# LCD_Keypad.net
KiCad netlist of a schematic drawn in Altium Designer
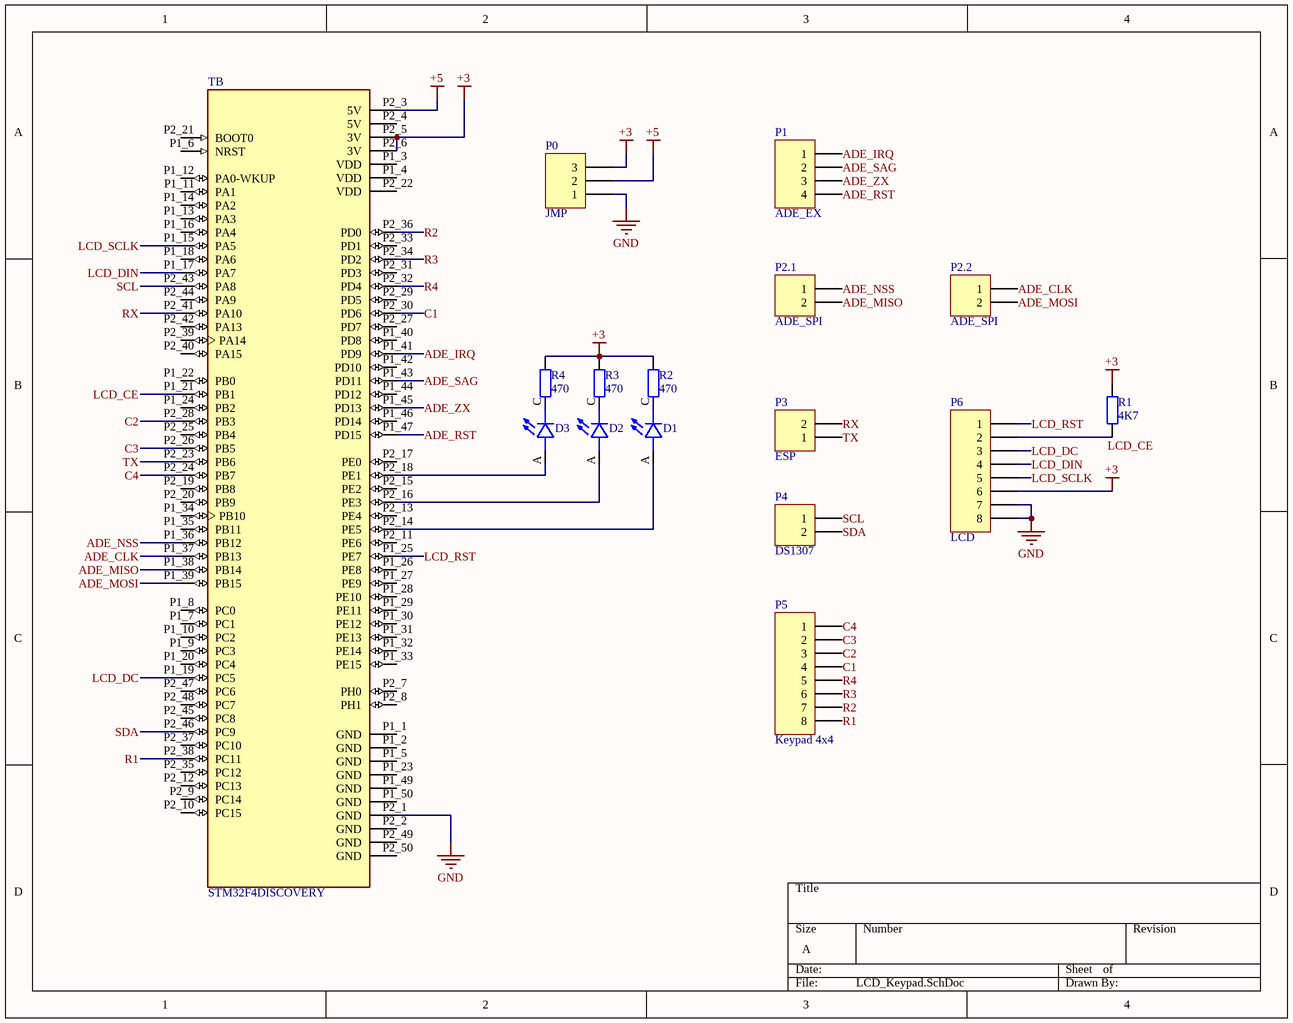
[diagram p0: LCD_Keypad.SchDoc]

(export (version "E")
  (design (tool "Eeschema 10.0.6"))
  (components
    (comp (ref "D1")
      (value "L08R5000Q1")
      (footprint "LEDRD254W57D500H1070")
      (description "LED, Orange, Through Hole, T-1 3/4 (5mm), 30 mA, 2.1 V, 635 nm")
      (fields (field (name "MF") "{'manufacturer': u'LED Technology'}"))
      (libsource (lib "LED_L08R5000Q1") (part "L08R5000Q1"))
    )
    (comp (ref "D2")
      (value "L08R5000Q1")
      (footprint "LEDRD254W57D500H1070")
      (description "LED, Orange, Through Hole, T-1 3/4 (5mm), 30 mA, 2.1 V, 635 nm")
      (fields (field (name "MF") "{'manufacturer': u'LED Technology'}"))
      (libsource (lib "LED_L08R5000Q1") (part "L08R5000Q1"))
    )
    (comp (ref "D3")
      (value "L08R5000Q1")
      (footprint "LEDRD254W57D500H1070")
      (description "LED, Orange, Through Hole, T-1 3/4 (5mm), 30 mA, 2.1 V, 635 nm")
      (fields (field (name "MF") "{'manufacturer': u'LED Technology'}"))
      (libsource (lib "LED_L08R5000Q1") (part "L08R5000Q1"))
    )
    (comp (ref "P0")
      (value "JMP")
      (footprint "HDR1X3")
      (description "Header, 3-Pin")
      (fields (field (name "PUBLISHER") "Altium Limited"))
      (libsource (lib "Miscellaneous Connectors") (part "Header 3"))
    )
    (comp (ref "P1")
      (value "ADE_EX")
      (footprint "HDR1X4")
      (description "Header, 4-Pin")
      (fields (field (name "PUBLISHER") "Altium Limited"))
      (libsource (lib "Miscellaneous Connectors") (part "Header 4"))
    )
    (comp (ref "P2.1")
      (value "ADE_SPI")
      (footprint "HDR1X2")
      (description "Header, 2-Pin")
      (fields (field (name "PUBLISHER") "Altium Limited"))
      (libsource (lib "Miscellaneous Connectors") (part "Header 2"))
    )
    (comp (ref "P2.2")
      (value "ADE_SPI")
      (footprint "HDR1X2")
      (description "Header, 2-Pin")
      (fields (field (name "PUBLISHER") "Altium Limited"))
      (libsource (lib "Miscellaneous Connectors") (part "Header 2"))
    )
    (comp (ref "P3")
      (value "ESP")
      (footprint "HDR1X2")
      (description "Header, 2-Pin")
      (fields (field (name "PUBLISHER") "Altium Limited"))
      (libsource (lib "") (part "Header 2_1"))
    )
    (comp (ref "P4")
      (value "DS1307")
      (footprint "HDR1X2")
      (description "Header, 2-Pin")
      (fields (field (name "PUBLISHER") "Altium Limited"))
      (libsource (lib "Miscellaneous Connectors") (part "Header 2"))
    )
    (comp (ref "P5")
      (value "Keypad 4x4")
      (footprint "HDR1X8")
      (description "Header, 8-Pin")
      (fields (field (name "PUBLISHER") "Altium Limited"))
      (libsource (lib "Miscellaneous Connectors") (part "Header 8"))
    )
    (comp (ref "P6")
      (value "LCD")
      (footprint "HDR1X8")
      (description "Header, 8-Pin")
      (fields (field (name "PUBLISHER") "Altium Limited"))
      (libsource (lib "Miscellaneous Connectors") (part "Header 8"))
    )
    (comp (ref "R1")
      (value "4K7")
      (footprint "AXIAL-0.4")
      (description "Resistor")
      (fields (field (name "Comment") "Res2") (field (name "PUBLISHER") "Altium Limited"))
      (libsource (lib "") (part "Res2_1"))
    )
    (comp (ref "R2")
      (value "470")
      (footprint "AXIAL-0.4")
      (description "Resistor")
      (fields (field (name "Comment") "Res2") (field (name "PUBLISHER") "Altium Limited"))
      (libsource (lib "Miscellaneous Devices") (part "Res2"))
    )
    (comp (ref "R3")
      (value "470")
      (footprint "AXIAL-0.4")
      (description "Resistor")
      (fields (field (name "Comment") "Res2") (field (name "PUBLISHER") "Altium Limited"))
      (libsource (lib "Miscellaneous Devices") (part "Res2"))
    )
    (comp (ref "R4")
      (value "470")
      (footprint "AXIAL-0.4")
      (description "Resistor")
      (fields (field (name "Comment") "Res2") (field (name "PUBLISHER") "Altium Limited"))
      (libsource (lib "Miscellaneous Devices") (part "Res2"))
    )
    (comp (ref "TB")
      (value "STM32F4DISCOVERY")
      (footprint "MODULE_STM32F4DISCOVERY")
      (description "STM32F407VGT6 Discovery STM32F4 ARMÂ® CortexÂ®-M4 MCU 32-Bit Embedded Evaluation Board")
      (fields (field (name "MF") "STMicroelectronics"))
      (libsource (lib "STM32F4DISCOVERY") (part "STM32F4DISCOVERY"))
    )
  )
  (nets
    (net (code "1") (name "+3") (class "Default")
      (node (ref "P0") (pin "3") (pinfunction "3_3") (pintype "passive"))
      (node (ref "P6") (pin "6") (pinfunction "6_6") (pintype "passive"))
      (node (ref "R1") (pin "2") (pinfunction "2_2") (pintype "passive"))
      (node (ref "R2") (pin "1") (pinfunction "1_1") (pintype "passive"))
      (node (ref "R3") (pin "1") (pinfunction "1_1") (pintype "passive"))
      (node (ref "R4") (pin "1") (pinfunction "1_1") (pintype "passive"))
      (node (ref "TB") (pin "P2_5") (pinfunction "3V_P2_5") (pintype "power_in"))
      (node (ref "TB") (pin "P2_6") (pinfunction "3V_P2_6") (pintype "power_in"))
    )
    (net (code "2") (name "+5") (class "Default")
      (node (ref "P0") (pin "2") (pinfunction "2_2") (pintype "passive"))
      (node (ref "TB") (pin "P2_3") (pinfunction "5V_P2_3") (pintype "power_in"))
    )
    (net (code "3") (name "/ADE_CLK") (class "Default")
      (node (ref "P2.2") (pin "1") (pinfunction "1_1") (pintype "passive"))
      (node (ref "TB") (pin "P1_37") (pinfunction "PB13_P1_37") (pintype "bidirectional"))
    )
    (net (code "4") (name "/ADE_IRQ") (class "Default")
      (node (ref "P1") (pin "1") (pinfunction "1_1") (pintype "passive"))
      (node (ref "TB") (pin "P1_41") (pinfunction "PD9_P1_41") (pintype "bidirectional"))
    )
    (net (code "5") (name "/ADE_MISO") (class "Default")
      (node (ref "P2.1") (pin "2") (pinfunction "2_2") (pintype "passive"))
      (node (ref "TB") (pin "P1_38") (pinfunction "PB14_P1_38") (pintype "bidirectional"))
    )
    (net (code "6") (name "/ADE_MOSI") (class "Default")
      (node (ref "P2.2") (pin "2") (pinfunction "2_2") (pintype "passive"))
      (node (ref "TB") (pin "P1_39") (pinfunction "PB15_P1_39") (pintype "bidirectional"))
    )
    (net (code "7") (name "/ADE_NSS") (class "Default")
      (node (ref "P2.1") (pin "1") (pinfunction "1_1") (pintype "passive"))
      (node (ref "TB") (pin "P1_36") (pinfunction "PB12_P1_36") (pintype "bidirectional"))
    )
    (net (code "8") (name "/ADE_RST") (class "Default")
      (node (ref "P1") (pin "4") (pinfunction "4_4") (pintype "passive"))
      (node (ref "TB") (pin "P1_47") (pinfunction "PD15_P1_47") (pintype "bidirectional"))
    )
    (net (code "9") (name "/ADE_SAG") (class "Default")
      (node (ref "P1") (pin "2") (pinfunction "2_2") (pintype "passive"))
      (node (ref "TB") (pin "P1_43") (pinfunction "PD11_P1_43") (pintype "bidirectional"))
    )
    (net (code "10") (name "/ADE_ZX") (class "Default")
      (node (ref "P1") (pin "3") (pinfunction "3_3") (pintype "passive"))
      (node (ref "TB") (pin "P1_45") (pinfunction "PD13_P1_45") (pintype "bidirectional"))
    )
    (net (code "11") (name "/C1") (class "Default")
      (node (ref "P5") (pin "4") (pinfunction "4_4") (pintype "passive"))
      (node (ref "TB") (pin "P2_30") (pinfunction "PD6_P2_30") (pintype "bidirectional"))
    )
    (net (code "12") (name "/C2") (class "Default")
      (node (ref "P5") (pin "3") (pinfunction "3_3") (pintype "passive"))
      (node (ref "TB") (pin "P2_28") (pinfunction "PB3_P2_28") (pintype "bidirectional"))
    )
    (net (code "13") (name "/C3") (class "Default")
      (node (ref "P5") (pin "2") (pinfunction "2_2") (pintype "passive"))
      (node (ref "TB") (pin "P2_26") (pinfunction "PB5_P2_26") (pintype "bidirectional"))
    )
    (net (code "14") (name "/C4") (class "Default")
      (node (ref "P5") (pin "1") (pinfunction "1_1") (pintype "passive"))
      (node (ref "TB") (pin "P2_24") (pinfunction "PB7_P2_24") (pintype "bidirectional"))
    )
    (net (code "15") (name "/LCD_CE") (class "Default")
      (node (ref "P6") (pin "2") (pinfunction "2_2") (pintype "passive"))
      (node (ref "R1") (pin "1") (pinfunction "1_1") (pintype "passive"))
      (node (ref "TB") (pin "P1_21") (pinfunction "PB1_P1_21") (pintype "bidirectional"))
    )
    (net (code "16") (name "/LCD_DC") (class "Default")
      (node (ref "P6") (pin "3") (pinfunction "3_3") (pintype "passive"))
      (node (ref "TB") (pin "P1_19") (pinfunction "PC5_P1_19") (pintype "bidirectional"))
    )
    (net (code "17") (name "/LCD_DIN") (class "Default")
      (node (ref "P6") (pin "4") (pinfunction "4_4") (pintype "passive"))
      (node (ref "TB") (pin "P1_17") (pinfunction "PA7_P1_17") (pintype "bidirectional"))
    )
    (net (code "18") (name "/LCD_RST") (class "Default")
      (node (ref "P6") (pin "1") (pinfunction "1_1") (pintype "passive"))
      (node (ref "TB") (pin "P1_25") (pinfunction "PE7_P1_25") (pintype "bidirectional"))
    )
    (net (code "19") (name "/LCD_SCLK") (class "Default")
      (node (ref "P6") (pin "5") (pinfunction "5_5") (pintype "passive"))
      (node (ref "TB") (pin "P1_15") (pinfunction "PA5_P1_15") (pintype "bidirectional"))
    )
    (net (code "20") (name "/R1") (class "Default")
      (node (ref "P5") (pin "8") (pinfunction "8_8") (pintype "passive"))
      (node (ref "TB") (pin "P2_38") (pinfunction "PC11_P2_38") (pintype "bidirectional"))
    )
    (net (code "21") (name "/R2") (class "Default")
      (node (ref "P5") (pin "7") (pinfunction "7_7") (pintype "passive"))
      (node (ref "TB") (pin "P2_36") (pinfunction "PD0_P2_36") (pintype "bidirectional"))
    )
    (net (code "22") (name "/R3") (class "Default")
      (node (ref "P5") (pin "6") (pinfunction "6_6") (pintype "passive"))
      (node (ref "TB") (pin "P2_34") (pinfunction "PD2_P2_34") (pintype "bidirectional"))
    )
    (net (code "23") (name "/R4") (class "Default")
      (node (ref "P5") (pin "5") (pinfunction "5_5") (pintype "passive"))
      (node (ref "TB") (pin "P2_32") (pinfunction "PD4_P2_32") (pintype "bidirectional"))
    )
    (net (code "24") (name "/RX") (class "Default")
      (node (ref "P3") (pin "2") (pinfunction "2_2") (pintype "passive"))
      (node (ref "TB") (pin "P2_41") (pinfunction "PA10_P2_41") (pintype "bidirectional"))
    )
    (net (code "25") (name "/SCL") (class "Default")
      (node (ref "P4") (pin "1") (pinfunction "1_1") (pintype "passive"))
      (node (ref "TB") (pin "P2_43") (pinfunction "PA8_P2_43") (pintype "bidirectional"))
    )
    (net (code "26") (name "/SDA") (class "Default")
      (node (ref "P4") (pin "2") (pinfunction "2_2") (pintype "passive"))
      (node (ref "TB") (pin "P2_46") (pinfunction "PC9_P2_46") (pintype "bidirectional"))
    )
    (net (code "27") (name "/TX") (class "Default")
      (node (ref "P3") (pin "1") (pinfunction "1_1") (pintype "passive"))
      (node (ref "TB") (pin "P2_23") (pinfunction "PB6_P2_23") (pintype "bidirectional"))
    )
    (net (code "28") (name "GND") (class "Default")
      (node (ref "P0") (pin "1") (pinfunction "1_1") (pintype "passive"))
      (node (ref "P6") (pin "7") (pinfunction "7_7") (pintype "passive"))
      (node (ref "P6") (pin "8") (pinfunction "8_8") (pintype "passive"))
      (node (ref "TB") (pin "P2_1") (pinfunction "GND_P2_1") (pintype "power_in"))
    )
    (net (code "29") (name "Net-(D1-PadC)") (class "Default")
      (node (ref "D1") (pin "C") (pinfunction "C_C") (pintype "passive"))
      (node (ref "R2") (pin "2") (pinfunction "2_2") (pintype "passive"))
    )
    (net (code "30") (name "Net-(D2-PadC)") (class "Default")
      (node (ref "D2") (pin "C") (pinfunction "C_C") (pintype "passive"))
      (node (ref "R3") (pin "2") (pinfunction "2_2") (pintype "passive"))
    )
    (net (code "31") (name "Net-(D3-PadC)") (class "Default")
      (node (ref "D3") (pin "C") (pinfunction "C_C") (pintype "passive"))
      (node (ref "R4") (pin "2") (pinfunction "2_2") (pintype "passive"))
    )
    (net (code "32") (name "Net-(TB-PE1)") (class "Default")
      (node (ref "D3") (pin "A") (pinfunction "A_A") (pintype "passive"))
      (node (ref "TB") (pin "P2_18") (pinfunction "PE1_P2_18") (pintype "bidirectional"))
    )
    (net (code "33") (name "Net-(TB-PE3)") (class "Default")
      (node (ref "D2") (pin "A") (pinfunction "A_A") (pintype "passive"))
      (node (ref "TB") (pin "P2_16") (pinfunction "PE3_P2_16") (pintype "bidirectional"))
    )
    (net (code "34") (name "Net-(TB-PE5)") (class "Default")
      (node (ref "D1") (pin "A") (pinfunction "A_A") (pintype "passive"))
      (node (ref "TB") (pin "P2_14") (pinfunction "PE5_P2_14") (pintype "bidirectional"))
    )
    (net (code "35") (name "unconnected-(TB-5V-PadP2_4)") (class "Default")
      (node (ref "TB") (pin "P2_4") (pinfunction "5V_P2_4") (pintype "power_in"))
    )
    (net (code "36") (name "unconnected-(TB-BOOT0-PadP2_21)") (class "Default")
      (node (ref "TB") (pin "P2_21") (pinfunction "BOOT0_P2_21") (pintype "input"))
    )
    (net (code "37") (name "unconnected-(TB-GND-PadP1_1)") (class "Default")
      (node (ref "TB") (pin "P1_1") (pinfunction "GND_P1_1") (pintype "power_in"))
    )
    (net (code "38") (name "unconnected-(TB-GND-PadP1_2)") (class "Default")
      (node (ref "TB") (pin "P1_2") (pinfunction "GND_P1_2") (pintype "power_in"))
    )
    (net (code "39") (name "unconnected-(TB-GND-PadP1_5)") (class "Default")
      (node (ref "TB") (pin "P1_5") (pinfunction "GND_P1_5") (pintype "power_in"))
    )
    (net (code "40") (name "unconnected-(TB-GND-PadP1_23)") (class "Default")
      (node (ref "TB") (pin "P1_23") (pinfunction "GND_P1_23") (pintype "power_in"))
    )
    (net (code "41") (name "unconnected-(TB-GND-PadP1_49)") (class "Default")
      (node (ref "TB") (pin "P1_49") (pinfunction "GND_P1_49") (pintype "power_in"))
    )
    (net (code "42") (name "unconnected-(TB-GND-PadP1_50)") (class "Default")
      (node (ref "TB") (pin "P1_50") (pinfunction "GND_P1_50") (pintype "power_in"))
    )
    (net (code "43") (name "unconnected-(TB-GND-PadP2_2)") (class "Default")
      (node (ref "TB") (pin "P2_2") (pinfunction "GND_P2_2") (pintype "power_in"))
    )
    (net (code "44") (name "unconnected-(TB-GND-PadP2_49)") (class "Default")
      (node (ref "TB") (pin "P2_49") (pinfunction "GND_P2_49") (pintype "power_in"))
    )
    (net (code "45") (name "unconnected-(TB-GND-PadP2_50)") (class "Default")
      (node (ref "TB") (pin "P2_50") (pinfunction "GND_P2_50") (pintype "power_in"))
    )
    (net (code "46") (name "unconnected-(TB-NRST-PadP1_6)") (class "Default")
      (node (ref "TB") (pin "P1_6") (pinfunction "NRST_P1_6") (pintype "input"))
    )
    (net (code "47") (name "unconnected-(TB-PA0-WKUP-PadP1_12)") (class "Default")
      (node (ref "TB") (pin "P1_12") (pinfunction "PA0-WKUP_P1_12") (pintype "bidirectional"))
    )
    (net (code "48") (name "unconnected-(TB-PA1-PadP1_11)") (class "Default")
      (node (ref "TB") (pin "P1_11") (pinfunction "PA1_P1_11") (pintype "bidirectional"))
    )
    (net (code "49") (name "unconnected-(TB-PA2-PadP1_14)") (class "Default")
      (node (ref "TB") (pin "P1_14") (pinfunction "PA2_P1_14") (pintype "bidirectional"))
    )
    (net (code "50") (name "unconnected-(TB-PA3-PadP1_13)") (class "Default")
      (node (ref "TB") (pin "P1_13") (pinfunction "PA3_P1_13") (pintype "bidirectional"))
    )
    (net (code "51") (name "unconnected-(TB-PA4-PadP1_16)") (class "Default")
      (node (ref "TB") (pin "P1_16") (pinfunction "PA4_P1_16") (pintype "bidirectional"))
    )
    (net (code "52") (name "unconnected-(TB-PA6-PadP1_18)") (class "Default")
      (node (ref "TB") (pin "P1_18") (pinfunction "PA6_P1_18") (pintype "bidirectional"))
    )
    (net (code "53") (name "unconnected-(TB-PA9-PadP2_44)") (class "Default")
      (node (ref "TB") (pin "P2_44") (pinfunction "PA9_P2_44") (pintype "bidirectional"))
    )
    (net (code "54") (name "unconnected-(TB-PA13-PadP2_42)") (class "Default")
      (node (ref "TB") (pin "P2_42") (pinfunction "PA13_P2_42") (pintype "bidirectional"))
    )
    (net (code "55") (name "unconnected-(TB-PA14-PadP2_39)") (class "Default")
      (node (ref "TB") (pin "P2_39") (pinfunction "PA14_P2_39") (pintype "bidirectional"))
    )
    (net (code "56") (name "unconnected-(TB-PA15-PadP2_40)") (class "Default")
      (node (ref "TB") (pin "P2_40") (pinfunction "PA15_P2_40") (pintype "bidirectional"))
    )
    (net (code "57") (name "unconnected-(TB-PB0-PadP1_22)") (class "Default")
      (node (ref "TB") (pin "P1_22") (pinfunction "PB0_P1_22") (pintype "bidirectional"))
    )
    (net (code "58") (name "unconnected-(TB-PB2-PadP1_24)") (class "Default")
      (node (ref "TB") (pin "P1_24") (pinfunction "PB2_P1_24") (pintype "bidirectional"))
    )
    (net (code "59") (name "unconnected-(TB-PB4-PadP2_25)") (class "Default")
      (node (ref "TB") (pin "P2_25") (pinfunction "PB4_P2_25") (pintype "bidirectional"))
    )
    (net (code "60") (name "unconnected-(TB-PB8-PadP2_19)") (class "Default")
      (node (ref "TB") (pin "P2_19") (pinfunction "PB8_P2_19") (pintype "bidirectional"))
    )
    (net (code "61") (name "unconnected-(TB-PB9-PadP2_20)") (class "Default")
      (node (ref "TB") (pin "P2_20") (pinfunction "PB9_P2_20") (pintype "bidirectional"))
    )
    (net (code "62") (name "unconnected-(TB-PB10-PadP1_34)") (class "Default")
      (node (ref "TB") (pin "P1_34") (pinfunction "PB10_P1_34") (pintype "bidirectional"))
    )
    (net (code "63") (name "unconnected-(TB-PB11-PadP1_35)") (class "Default")
      (node (ref "TB") (pin "P1_35") (pinfunction "PB11_P1_35") (pintype "bidirectional"))
    )
    (net (code "64") (name "unconnected-(TB-PC0-PadP1_8)") (class "Default")
      (node (ref "TB") (pin "P1_8") (pinfunction "PC0_P1_8") (pintype "bidirectional"))
    )
    (net (code "65") (name "unconnected-(TB-PC1-PadP1_7)") (class "Default")
      (node (ref "TB") (pin "P1_7") (pinfunction "PC1_P1_7") (pintype "bidirectional"))
    )
    (net (code "66") (name "unconnected-(TB-PC2-PadP1_10)") (class "Default")
      (node (ref "TB") (pin "P1_10") (pinfunction "PC2_P1_10") (pintype "bidirectional"))
    )
    (net (code "67") (name "unconnected-(TB-PC3-PadP1_9)") (class "Default")
      (node (ref "TB") (pin "P1_9") (pinfunction "PC3_P1_9") (pintype "bidirectional"))
    )
    (net (code "68") (name "unconnected-(TB-PC4-PadP1_20)") (class "Default")
      (node (ref "TB") (pin "P1_20") (pinfunction "PC4_P1_20") (pintype "bidirectional"))
    )
    (net (code "69") (name "unconnected-(TB-PC6-PadP2_47)") (class "Default")
      (node (ref "TB") (pin "P2_47") (pinfunction "PC6_P2_47") (pintype "bidirectional"))
    )
    (net (code "70") (name "unconnected-(TB-PC7-PadP2_48)") (class "Default")
      (node (ref "TB") (pin "P2_48") (pinfunction "PC7_P2_48") (pintype "bidirectional"))
    )
    (net (code "71") (name "unconnected-(TB-PC8-PadP2_45)") (class "Default")
      (node (ref "TB") (pin "P2_45") (pinfunction "PC8_P2_45") (pintype "bidirectional"))
    )
    (net (code "72") (name "unconnected-(TB-PC10-PadP2_37)") (class "Default")
      (node (ref "TB") (pin "P2_37") (pinfunction "PC10_P2_37") (pintype "bidirectional"))
    )
    (net (code "73") (name "unconnected-(TB-PC12-PadP2_35)") (class "Default")
      (node (ref "TB") (pin "P2_35") (pinfunction "PC12_P2_35") (pintype "bidirectional"))
    )
    (net (code "74") (name "unconnected-(TB-PC13-PadP2_12)") (class "Default")
      (node (ref "TB") (pin "P2_12") (pinfunction "PC13_P2_12") (pintype "bidirectional"))
    )
    (net (code "75") (name "unconnected-(TB-PC14-PadP2_9)") (class "Default")
      (node (ref "TB") (pin "P2_9") (pinfunction "PC14_P2_9") (pintype "bidirectional"))
    )
    (net (code "76") (name "unconnected-(TB-PC15-PadP2_10)") (class "Default")
      (node (ref "TB") (pin "P2_10") (pinfunction "PC15_P2_10") (pintype "bidirectional"))
    )
    (net (code "77") (name "unconnected-(TB-PD1-PadP2_33)") (class "Default")
      (node (ref "TB") (pin "P2_33") (pinfunction "PD1_P2_33") (pintype "bidirectional"))
    )
    (net (code "78") (name "unconnected-(TB-PD3-PadP2_31)") (class "Default")
      (node (ref "TB") (pin "P2_31") (pinfunction "PD3_P2_31") (pintype "bidirectional"))
    )
    (net (code "79") (name "unconnected-(TB-PD5-PadP2_29)") (class "Default")
      (node (ref "TB") (pin "P2_29") (pinfunction "PD5_P2_29") (pintype "bidirectional"))
    )
    (net (code "80") (name "unconnected-(TB-PD7-PadP2_27)") (class "Default")
      (node (ref "TB") (pin "P2_27") (pinfunction "PD7_P2_27") (pintype "bidirectional"))
    )
    (net (code "81") (name "unconnected-(TB-PD8-PadP1_40)") (class "Default")
      (node (ref "TB") (pin "P1_40") (pinfunction "PD8_P1_40") (pintype "bidirectional"))
    )
    (net (code "82") (name "unconnected-(TB-PD10-PadP1_42)") (class "Default")
      (node (ref "TB") (pin "P1_42") (pinfunction "PD10_P1_42") (pintype "bidirectional"))
    )
    (net (code "83") (name "unconnected-(TB-PD12-PadP1_44)") (class "Default")
      (node (ref "TB") (pin "P1_44") (pinfunction "PD12_P1_44") (pintype "bidirectional"))
    )
    (net (code "84") (name "unconnected-(TB-PD14-PadP1_46)") (class "Default")
      (node (ref "TB") (pin "P1_46") (pinfunction "PD14_P1_46") (pintype "bidirectional"))
    )
    (net (code "85") (name "unconnected-(TB-PE0-PadP2_17)") (class "Default")
      (node (ref "TB") (pin "P2_17") (pinfunction "PE0_P2_17") (pintype "bidirectional"))
    )
    (net (code "86") (name "unconnected-(TB-PE2-PadP2_15)") (class "Default")
      (node (ref "TB") (pin "P2_15") (pinfunction "PE2_P2_15") (pintype "bidirectional"))
    )
    (net (code "87") (name "unconnected-(TB-PE4-PadP2_13)") (class "Default")
      (node (ref "TB") (pin "P2_13") (pinfunction "PE4_P2_13") (pintype "bidirectional"))
    )
    (net (code "88") (name "unconnected-(TB-PE6-PadP2_11)") (class "Default")
      (node (ref "TB") (pin "P2_11") (pinfunction "PE6_P2_11") (pintype "bidirectional"))
    )
    (net (code "89") (name "unconnected-(TB-PE8-PadP1_26)") (class "Default")
      (node (ref "TB") (pin "P1_26") (pinfunction "PE8_P1_26") (pintype "bidirectional"))
    )
    (net (code "90") (name "unconnected-(TB-PE9-PadP1_27)") (class "Default")
      (node (ref "TB") (pin "P1_27") (pinfunction "PE9_P1_27") (pintype "bidirectional"))
    )
    (net (code "91") (name "unconnected-(TB-PE10-PadP1_28)") (class "Default")
      (node (ref "TB") (pin "P1_28") (pinfunction "PE10_P1_28") (pintype "bidirectional"))
    )
    (net (code "92") (name "unconnected-(TB-PE11-PadP1_29)") (class "Default")
      (node (ref "TB") (pin "P1_29") (pinfunction "PE11_P1_29") (pintype "bidirectional"))
    )
    (net (code "93") (name "unconnected-(TB-PE12-PadP1_30)") (class "Default")
      (node (ref "TB") (pin "P1_30") (pinfunction "PE12_P1_30") (pintype "bidirectional"))
    )
    (net (code "94") (name "unconnected-(TB-PE13-PadP1_31)") (class "Default")
      (node (ref "TB") (pin "P1_31") (pinfunction "PE13_P1_31") (pintype "bidirectional"))
    )
    (net (code "95") (name "unconnected-(TB-PE14-PadP1_32)") (class "Default")
      (node (ref "TB") (pin "P1_32") (pinfunction "PE14_P1_32") (pintype "bidirectional"))
    )
    (net (code "96") (name "unconnected-(TB-PE15-PadP1_33)") (class "Default")
      (node (ref "TB") (pin "P1_33") (pinfunction "PE15_P1_33") (pintype "bidirectional"))
    )
    (net (code "97") (name "unconnected-(TB-PH0-PadP2_7)") (class "Default")
      (node (ref "TB") (pin "P2_7") (pinfunction "PH0_P2_7") (pintype "bidirectional"))
    )
    (net (code "98") (name "unconnected-(TB-PH1-PadP2_8)") (class "Default")
      (node (ref "TB") (pin "P2_8") (pinfunction "PH1_P2_8") (pintype "bidirectional"))
    )
    (net (code "99") (name "unconnected-(TB-VDD-PadP1_3)") (class "Default")
      (node (ref "TB") (pin "P1_3") (pinfunction "VDD_P1_3") (pintype "power_in"))
    )
    (net (code "100") (name "unconnected-(TB-VDD-PadP1_4)") (class "Default")
      (node (ref "TB") (pin "P1_4") (pinfunction "VDD_P1_4") (pintype "power_in"))
    )
    (net (code "101") (name "unconnected-(TB-VDD-PadP2_22)") (class "Default")
      (node (ref "TB") (pin "P2_22") (pinfunction "VDD_P2_22") (pintype "power_in"))
    )
  )
)
